# Maximizer.net
KiCad netlist of a schematic drawn in Altium Designer
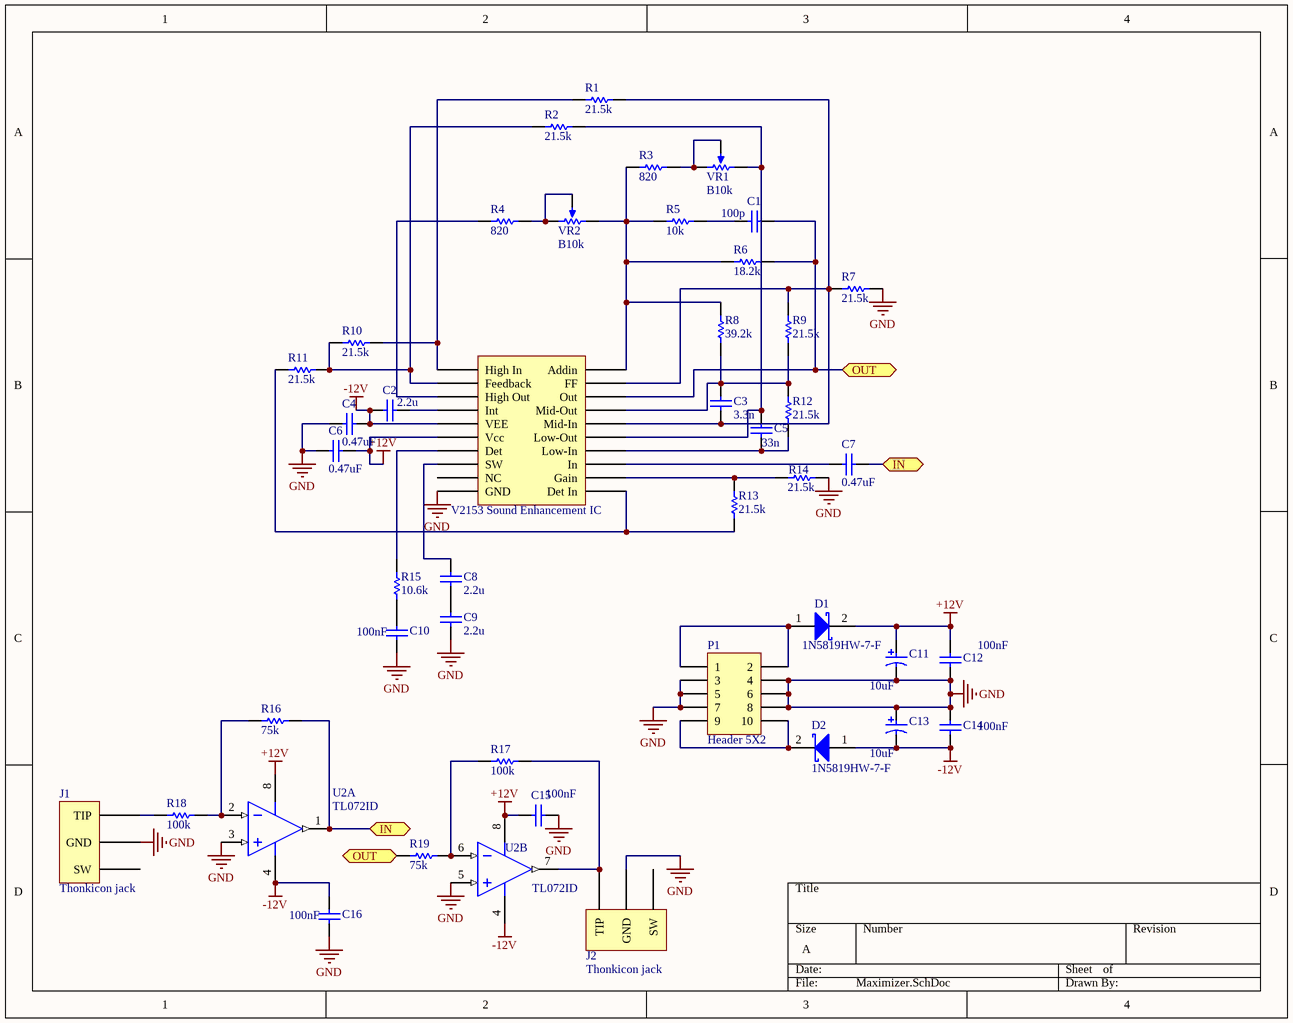
[diagram p0: Maximizer.SchDoc]

(export (version "E")
  (design (tool "Eeschema 10.0.6"))
  (components
    (comp (ref "C1")
      (value "100p")
      (footprint "CAPC0603(1608)100_M")
      (description "CAP")
      (fields (field (name "MFR") "AVX") (field (name "Comment") "100pF"))
      (libsource (lib "Altium Content Vault") (part "CMP-1035-00002-1"))
    )
    (comp (ref "C2")
      (value "2.2u")
      (footprint "CAPC0603(1608)100_M")
      (description "CAP")
      (fields (field (name "MFR") "Murata") (field (name "Comment") "2.2uF"))
      (libsource (lib "Altium Content Vault") (part "CMP-1035-00002-1"))
    )
    (comp (ref "C3")
      (value "3.3n")
      (footprint "CAPC0603(1608)100_M")
      (description "CAP")
      (fields (field (name "MFR") "AVX") (field (name "Comment") "3.3nF"))
      (libsource (lib "Altium Content Vault") (part "CMP-1035-00002-1"))
    )
    (comp (ref "C4")
      (value "0.47uF")
      (footprint "CAPC0603(1608)100_M")
      (description "CAP")
      (fields (field (name "MFR") "Murata"))
      (libsource (lib "Altium Content Vault") (part "CMP-1035-00002-1"))
    )
    (comp (ref "C5")
      (value "33n")
      (footprint "CAPC0603(1608)100_M")
      (description "CAP")
      (fields (field (name "MFR") "Murata") (field (name "Comment") "33nF"))
      (libsource (lib "Altium Content Vault") (part "CMP-1035-00002-1"))
    )
    (comp (ref "C6")
      (value "0.47uF")
      (footprint "CAPC0603(1608)100_M")
      (description "CAP")
      (fields (field (name "MFR") "Murata"))
      (libsource (lib "Altium Content Vault") (part "CMP-1035-00002-1"))
    )
    (comp (ref "C7")
      (value "0.47uF")
      (footprint "CAPC0603(1608)100_M")
      (description "CAP")
      (fields (field (name "MFR") "Murata"))
      (libsource (lib "Altium Content Vault") (part "CMP-1035-00002-1"))
    )
    (comp (ref "C8")
      (value "2.2u")
      (footprint "CAPC0603(1608)100_M")
      (description "CAP")
      (fields (field (name "MFR") "Murata") (field (name "Comment") "2.2uF"))
      (libsource (lib "Altium Content Vault") (part "CMP-1035-00002-1"))
    )
    (comp (ref "C9")
      (value "2.2u")
      (footprint "CAPC0603(1608)100_M")
      (description "CAP")
      (fields (field (name "MFR") "Murata") (field (name "Comment") "2.2uF"))
      (libsource (lib "Altium Content Vault") (part "CMP-1035-00002-1"))
    )
    (comp (ref "C10")
      (value "100nF")
      (footprint "CAPC0603(1608)100_M")
      (description "CAP")
      (fields (field (name "MFR") "AVX"))
      (libsource (lib "Altium Content Vault") (part "CMP-1035-00002-1"))
    )
    (comp (ref "C11")
      (value "10uF")
      (footprint "NIC-CAPA2-4X5.8_V")
      (fields (field (name "MFR") "Nichicon"))
      (libsource (lib "Altium Content Vault") (part "CMP-0687-00016-1"))
    )
    (comp (ref "C12")
      (value "100nF")
      (footprint "CAPC0603(1608)100_M")
      (description "CAP")
      (fields (field (name "MFR") "AVX"))
      (libsource (lib "Altium Content Vault") (part "CMP-1035-00002-1"))
    )
    (comp (ref "C13")
      (value "10uF")
      (footprint "NIC-CAPA2-4X5.8_V")
      (fields (field (name "MFR") "Nichicon"))
      (libsource (lib "Altium Content Vault") (part "CMP-0687-00016-1"))
    )
    (comp (ref "C14")
      (value "100nF")
      (footprint "CAPC0603(1608)100_M")
      (description "CAP")
      (fields (field (name "MFR") "AVX"))
      (libsource (lib "Altium Content Vault") (part "CMP-1035-00002-1"))
    )
    (comp (ref "C15")
      (value "100nF")
      (footprint "CAPC0603(1608)100_M")
      (description "CAP")
      (fields (field (name "MFR") "AVX"))
      (libsource (lib "Altium Content Vault") (part "CMP-1035-00002-1"))
    )
    (comp (ref "C16")
      (value "100nF")
      (footprint "CAPC0603(1608)100_M")
      (description "CAP")
      (fields (field (name "MFR") "AVX"))
      (libsource (lib "Altium Content Vault") (part "CMP-1035-00002-1"))
    )
    (comp (ref "D1")
      (value "1N5819HW-7-F")
      (footprint "DIOD-SOD-123-2_V")
      (fields (field (name "MFR") "Diodes Inc."))
      (libsource (lib "Altium Content Vault") (part "CMP-0303-00003-1"))
    )
    (comp (ref "D2")
      (value "1N5819HW-7-F")
      (footprint "DIOD-SOD-123-2_V")
      (fields (field (name "MFR") "Diodes Inc."))
      (libsource (lib "Altium Content Vault") (part "CMP-0303-00003-1"))
    )
    (comp (ref "J1")
      (value "Thonkicon jack")
      (footprint "Thonkiconn Pot PJ301M")
      (libsource (lib "EurrackParts") (part "Thonkicon jack"))
    )
    (comp (ref "J2")
      (value "Thonkicon jack")
      (footprint "Thonkiconn Pot PJ301M")
      (libsource (lib "") (part "Thonkicon jack_1"))
    )
    (comp (ref "P1")
      (value "Header 5X2")
      (footprint "HDR2X5")
      (description "Header, 5-Pin, Dual row")
      (fields (field (name "PUBLISHER") "Altium Limited"))
      (libsource (lib "Miscellaneous Connectors") (part "Header 5X2"))
    )
    (comp (ref "R1")
      (value "21.5k")
      (footprint "RESC0603(1608)_M")
      (description "Res")
      (fields (field (name "TOLERANCE") "5 %") (field (name "MFR") "Susumu"))
      (libsource (lib "Altium Content Vault") (part "CMP-1012-00002-1"))
    )
    (comp (ref "R2")
      (value "21.5k")
      (footprint "RESC0603(1608)_M")
      (description "Res")
      (fields (field (name "TOLERANCE") "5 %") (field (name "MFR") "Susumu"))
      (libsource (lib "Altium Content Vault") (part "CMP-1012-00002-1"))
    )
    (comp (ref "R3")
      (value "820")
      (footprint "RESC0603(1608)_M")
      (description "Res")
      (fields (field (name "TOLERANCE") "5 %") (field (name "MFR") "Susumu"))
      (libsource (lib "Altium Content Vault") (part "CMP-1012-00002-1"))
    )
    (comp (ref "R4")
      (value "820")
      (footprint "RESC0603(1608)_M")
      (description "Res")
      (fields (field (name "TOLERANCE") "5 %") (field (name "MFR") "Susumu"))
      (libsource (lib "Altium Content Vault") (part "CMP-1012-00002-1"))
    )
    (comp (ref "R5")
      (value "10k")
      (footprint "RESC0603(1608)_M")
      (description "Res")
      (fields (field (name "TOLERANCE") "5 %") (field (name "MFR") "Susumu"))
      (libsource (lib "Altium Content Vault") (part "CMP-1012-00002-1"))
    )
    (comp (ref "R6")
      (value "18.2k")
      (footprint "RESC0603(1608)_M")
      (description "Res")
      (fields (field (name "TOLERANCE") "5 %") (field (name "MFR") "Susumu"))
      (libsource (lib "Altium Content Vault") (part "CMP-1012-00002-1"))
    )
    (comp (ref "R7")
      (value "21.5k")
      (footprint "RESC0603(1608)_M")
      (description "Res")
      (fields (field (name "TOLERANCE") "5 %") (field (name "MFR") "Susumu"))
      (libsource (lib "Altium Content Vault") (part "CMP-1012-00002-1"))
    )
    (comp (ref "R8")
      (value "39.2k")
      (footprint "RESC0603(1608)_M")
      (description "Res")
      (fields (field (name "TOLERANCE") "5 %") (field (name "MFR") "KOA"))
      (libsource (lib "Altium Content Vault") (part "CMP-1012-00002-1"))
    )
    (comp (ref "R9")
      (value "21.5k")
      (footprint "RESC0603(1608)_M")
      (description "Res")
      (fields (field (name "TOLERANCE") "5 %") (field (name "MFR") "Susumu"))
      (libsource (lib "Altium Content Vault") (part "CMP-1012-00002-1"))
    )
    (comp (ref "R10")
      (value "21.5k")
      (footprint "RESC0603(1608)_M")
      (description "Res")
      (fields (field (name "TOLERANCE") "5 %") (field (name "MFR") "Susumu"))
      (libsource (lib "Altium Content Vault") (part "CMP-1012-00002-1"))
    )
    (comp (ref "R11")
      (value "21.5k")
      (footprint "RESC0603(1608)_M")
      (description "Res")
      (fields (field (name "TOLERANCE") "5 %") (field (name "MFR") "Susumu"))
      (libsource (lib "Altium Content Vault") (part "CMP-1012-00002-1"))
    )
    (comp (ref "R12")
      (value "21.5k")
      (footprint "RESC0603(1608)_M")
      (description "Res")
      (fields (field (name "TOLERANCE") "5 %") (field (name "MFR") "Susumu"))
      (libsource (lib "Altium Content Vault") (part "CMP-1012-00002-1"))
    )
    (comp (ref "R13")
      (value "21.5k")
      (footprint "RESC0603(1608)_M")
      (description "Res")
      (fields (field (name "TOLERANCE") "5 %") (field (name "MFR") "Susumu"))
      (libsource (lib "Altium Content Vault") (part "CMP-1012-00002-1"))
    )
    (comp (ref "R14")
      (value "21.5k")
      (footprint "RESC0603(1608)_M")
      (description "Res")
      (fields (field (name "TOLERANCE") "5 %") (field (name "MFR") "Susumu"))
      (libsource (lib "Altium Content Vault") (part "CMP-1012-00002-1"))
    )
    (comp (ref "R15")
      (value "10.6k")
      (footprint "RESC0603(1608)_M")
      (description "Res")
      (fields (field (name "TOLERANCE") "5 %") (field (name "MFR") "Koa"))
      (libsource (lib "Altium Content Vault") (part "CMP-1012-00002-1"))
    )
    (comp (ref "R16")
      (value "75k")
      (footprint "RESC0603(1608)_M")
      (description "Res")
      (fields (field (name "TOLERANCE") "5 %") (field (name "MFR") "Susumu"))
      (libsource (lib "Altium Content Vault") (part "CMP-1012-00002-1"))
    )
    (comp (ref "R17")
      (value "100k")
      (footprint "RESC0603(1608)_M")
      (description "Res")
      (fields (field (name "TOLERANCE") "5 %") (field (name "MFR") "Susumu"))
      (libsource (lib "Altium Content Vault") (part "CMP-1012-00002-1"))
    )
    (comp (ref "R18")
      (value "100k")
      (footprint "RESC0603(1608)_M")
      (description "Res")
      (fields (field (name "TOLERANCE") "5 %") (field (name "MFR") "Susumu"))
      (libsource (lib "Altium Content Vault") (part "CMP-1012-00002-1"))
    )
    (comp (ref "R19")
      (value "75k")
      (footprint "RESC0603(1608)_M")
      (description "Res")
      (fields (field (name "TOLERANCE") "5 %") (field (name "MFR") "Susumu"))
      (libsource (lib "Altium Content Vault") (part "CMP-1012-00002-1"))
    )
    (comp (ref "U1")
      (value "V2153 Sound Enhancement IC")
      (footprint "SOIC20 - duplicate")
      (description "V2153")
      (libsource (lib "EurrackParts") (part "CoolaudioV2153"))
    )
    (comp (ref "U2")
      (value "TL072ID")
      (footprint "D0008A_N")
      (fields (field (name "MFR") "ST Micro"))
      (libsource (lib "Altium Content Vault") (part "CMP-0015-00077-2"))
    )
    (comp (ref "VR1")
      (value "B10k")
      (footprint "SonGueiPot")
      (fields (field (name "MANUFACTURER") "Bourns") (field (name "PARTNUMBER") "3006P-7-502ZLF"))
      (libsource (lib "altium-import") (part "root_0_BOUR-3006P-3_"))
    )
    (comp (ref "VR2")
      (value "B10k")
      (footprint "SonGueiPot")
      (fields (field (name "MANUFACTURER") "Bourns") (field (name "PARTNUMBER") "3006P-7-502ZLF"))
      (libsource (lib "altium-import") (part "root_0_BOUR-3006P-3_"))
    )
  )
  (nets
    (net (code "1") (name "+12V") (class "Default")
      (node (ref "C11") (pin "1") (pinfunction "1_1") (pintype "passive"))
      (node (ref "C12") (pin "1") (pinfunction "1_1") (pintype "passive"))
      (node (ref "C15") (pin "1") (pinfunction "1_1") (pintype "passive"))
      (node (ref "C6") (pin "2") (pinfunction "2_2") (pintype "passive"))
      (node (ref "D1") (pin "2") (pinfunction "K_2") (pintype "passive"))
      (node (ref "U1") (pin "6") (pinfunction "Vcc_6") (pintype "passive"))
      (node (ref "U2") (pin "8") (pinfunction "VCC+_8") (pintype "power_in"))
    )
    (net (code "2") (name "-12V") (class "Default")
      (node (ref "C13") (pin "2") (pinfunction "2_2") (pintype "passive"))
      (node (ref "C14") (pin "2") (pinfunction "2_2") (pintype "passive"))
      (node (ref "C16") (pin "1") (pinfunction "1_1") (pintype "passive"))
      (node (ref "C2") (pin "1") (pinfunction "1_1") (pintype "passive"))
      (node (ref "C4") (pin "2") (pinfunction "2_2") (pintype "passive"))
      (node (ref "D2") (pin "1") (pinfunction "A_1") (pintype "passive"))
      (node (ref "U1") (pin "5") (pinfunction "VEE_5") (pintype "passive"))
      (node (ref "U2") (pin "4") (pinfunction "VCC-_4") (pintype "power_in"))
    )
    (net (code "3") (name "/IN") (class "Default")
      (node (ref "C7") (pin "2") (pinfunction "2_2") (pintype "passive"))
      (node (ref "R16") (pin "1") (pinfunction "1_1") (pintype "passive"))
      (node (ref "U2") (pin "1") (pinfunction "OUT1_1") (pintype "output"))
    )
    (net (code "4") (name "/OUT") (class "Default")
      (node (ref "C1") (pin "2") (pinfunction "2_2") (pintype "passive"))
      (node (ref "R19") (pin "2") (pinfunction "2_2") (pintype "passive"))
      (node (ref "R6") (pin "1") (pinfunction "1_1") (pintype "passive"))
      (node (ref "U1") (pin "18") (pinfunction "Out_18") (pintype "passive"))
    )
    (net (code "5") (name "GND") (class "Default")
      (node (ref "C10") (pin "2") (pinfunction "2_2") (pintype "passive"))
      (node (ref "C11") (pin "2") (pinfunction "2_2") (pintype "passive"))
      (node (ref "C12") (pin "2") (pinfunction "2_2") (pintype "passive"))
      (node (ref "C13") (pin "1") (pinfunction "1_1") (pintype "passive"))
      (node (ref "C14") (pin "1") (pinfunction "1_1") (pintype "passive"))
      (node (ref "C15") (pin "2") (pinfunction "2_2") (pintype "passive"))
      (node (ref "C16") (pin "2") (pinfunction "2_2") (pintype "passive"))
      (node (ref "C4") (pin "1") (pinfunction "1_1") (pintype "passive"))
      (node (ref "C6") (pin "1") (pinfunction "1_1") (pintype "passive"))
      (node (ref "C9") (pin "1") (pinfunction "1_1") (pintype "passive"))
      (node (ref "J1") (pin "1") (pinfunction "GND_1") (pintype "passive"))
      (node (ref "J2") (pin "1") (pinfunction "GND_1") (pintype "passive"))
      (node (ref "P1") (pin "3") (pinfunction "3_3") (pintype "passive"))
      (node (ref "P1") (pin "4") (pinfunction "4_4") (pintype "passive"))
      (node (ref "P1") (pin "5") (pinfunction "5_5") (pintype "passive"))
      (node (ref "P1") (pin "6") (pinfunction "6_6") (pintype "passive"))
      (node (ref "P1") (pin "7") (pinfunction "7_7") (pintype "passive"))
      (node (ref "P1") (pin "8") (pinfunction "8_8") (pintype "passive"))
      (node (ref "R14") (pin "1") (pinfunction "1_1") (pintype "passive"))
      (node (ref "R7") (pin "1") (pinfunction "1_1") (pintype "passive"))
      (node (ref "U1") (pin "10") (pinfunction "GND_10") (pintype "passive"))
      (node (ref "U2") (pin "3") (pinfunction "IN1+_3") (pintype "input"))
      (node (ref "U2") (pin "5") (pinfunction "IN2+_5") (pintype "input"))
    )
    (net (code "6") (name "Net-(C1-Pad1)") (class "Default")
      (node (ref "C1") (pin "1") (pinfunction "1_1") (pintype "passive"))
      (node (ref "R5") (pin "1") (pinfunction "1_1") (pintype "passive"))
    )
    (net (code "7") (name "Net-(C8-Pad1)") (class "Default")
      (node (ref "C8") (pin "1") (pinfunction "1_1") (pintype "passive"))
      (node (ref "C9") (pin "2") (pinfunction "2_2") (pintype "passive"))
    )
    (net (code "8") (name "Net-(C10-Pad1)") (class "Default")
      (node (ref "C10") (pin "1") (pinfunction "1_1") (pintype "passive"))
      (node (ref "R15") (pin "1") (pinfunction "1_1") (pintype "passive"))
    )
    (net (code "9") (name "Net-(D1-A)") (class "Default")
      (node (ref "D1") (pin "1") (pinfunction "A_1") (pintype "passive"))
      (node (ref "P1") (pin "1") (pinfunction "1_1") (pintype "passive"))
      (node (ref "P1") (pin "2") (pinfunction "2_2") (pintype "passive"))
    )
    (net (code "10") (name "Net-(D2-K)") (class "Default")
      (node (ref "D2") (pin "2") (pinfunction "K_2") (pintype "passive"))
      (node (ref "P1") (pin "10") (pinfunction "10_10") (pintype "passive"))
      (node (ref "P1") (pin "9") (pinfunction "9_9") (pintype "passive"))
    )
    (net (code "11") (name "Net-(J1-TIP)") (class "Default")
      (node (ref "J1") (pin "3") (pinfunction "TIP_3") (pintype "passive"))
      (node (ref "R18") (pin "2") (pinfunction "2_2") (pintype "passive"))
    )
    (net (code "12") (name "Net-(J2-TIP)") (class "Default")
      (node (ref "J2") (pin "3") (pinfunction "TIP_3") (pintype "passive"))
      (node (ref "R17") (pin "1") (pinfunction "1_1") (pintype "passive"))
      (node (ref "U2") (pin "7") (pinfunction "OUT2_7") (pintype "output"))
    )
    (net (code "13") (name "Net-(U1-Addin)") (class "Default")
      (node (ref "R3") (pin "2") (pinfunction "2_2") (pintype "passive"))
      (node (ref "R5") (pin "2") (pinfunction "2_2") (pintype "passive"))
      (node (ref "R6") (pin "2") (pinfunction "2_2") (pintype "passive"))
      (node (ref "R8") (pin "2") (pinfunction "2_2") (pintype "passive"))
      (node (ref "U1") (pin "20") (pinfunction "Addin_20") (pintype "passive"))
      (node (ref "VR2") (pin "3") (pinfunction "CW_3") (pintype "passive"))
    )
    (net (code "14") (name "Net-(U1-Det)") (class "Default")
      (node (ref "R15") (pin "2") (pinfunction "2_2") (pintype "passive"))
      (node (ref "U1") (pin "7") (pinfunction "Det_7") (pintype "passive"))
    )
    (net (code "15") (name "Net-(U1-Det_In)") (class "Default")
      (node (ref "R11") (pin "2") (pinfunction "2_2") (pintype "passive"))
      (node (ref "R13") (pin "2") (pinfunction "2_2") (pintype "passive"))
      (node (ref "U1") (pin "11") (pinfunction "Det_In_11") (pintype "passive"))
    )
    (net (code "16") (name "Net-(U1-FF)") (class "Default")
      (node (ref "C3") (pin "1") (pinfunction "1_1") (pintype "passive"))
      (node (ref "R1") (pin "1") (pinfunction "1_1") (pintype "passive"))
      (node (ref "R7") (pin "2") (pinfunction "2_2") (pintype "passive"))
      (node (ref "R9") (pin "1") (pinfunction "1_1") (pintype "passive"))
      (node (ref "U1") (pin "16") (pinfunction "Mid-In_16") (pintype "passive"))
      (node (ref "U1") (pin "19") (pinfunction "FF_19") (pintype "passive"))
    )
    (net (code "17") (name "Net-(U1-Feedback)") (class "Default")
      (node (ref "R10") (pin "2") (pinfunction "2_2") (pintype "passive"))
      (node (ref "R11") (pin "1") (pinfunction "1_1") (pintype "passive"))
      (node (ref "R2") (pin "2") (pinfunction "2_2") (pintype "passive"))
      (node (ref "U1") (pin "2") (pinfunction "Feedback_2") (pintype "passive"))
    )
    (net (code "18") (name "Net-(U1-Gain)") (class "Default")
      (node (ref "R13") (pin "1") (pinfunction "1_1") (pintype "passive"))
      (node (ref "R14") (pin "2") (pinfunction "2_2") (pintype "passive"))
      (node (ref "U1") (pin "12") (pinfunction "Gain_12") (pintype "passive"))
    )
    (net (code "19") (name "Net-(U1-High_In)") (class "Default")
      (node (ref "R1") (pin "2") (pinfunction "2_2") (pintype "passive"))
      (node (ref "R10") (pin "1") (pinfunction "1_1") (pintype "passive"))
      (node (ref "U1") (pin "1") (pinfunction "High_In_1") (pintype "passive"))
    )
    (net (code "20") (name "Net-(U1-High_Out)") (class "Default")
      (node (ref "R4") (pin "2") (pinfunction "2_2") (pintype "passive"))
      (node (ref "U1") (pin "3") (pinfunction "High_Out_3") (pintype "passive"))
    )
    (net (code "21") (name "Net-(U1-In)") (class "Default")
      (node (ref "C7") (pin "1") (pinfunction "1_1") (pintype "passive"))
      (node (ref "U1") (pin "13") (pinfunction "In_13") (pintype "passive"))
    )
    (net (code "22") (name "Net-(U1-Int)") (class "Default")
      (node (ref "C2") (pin "2") (pinfunction "2_2") (pintype "passive"))
      (node (ref "U1") (pin "4") (pinfunction "Int_4") (pintype "passive"))
    )
    (net (code "23") (name "Net-(U1-Low-In)") (class "Default")
      (node (ref "C5") (pin "1") (pinfunction "1_1") (pintype "passive"))
      (node (ref "R12") (pin "2") (pinfunction "2_2") (pintype "passive"))
      (node (ref "U1") (pin "14") (pinfunction "Low-In_14") (pintype "passive"))
    )
    (net (code "24") (name "Net-(U1-Low-Out)") (class "Default")
      (node (ref "C5") (pin "2") (pinfunction "2_2") (pintype "passive"))
      (node (ref "R2") (pin "1") (pinfunction "1_1") (pintype "passive"))
      (node (ref "U1") (pin "15") (pinfunction "Low-Out_15") (pintype "passive"))
      (node (ref "VR1") (pin "3") (pinfunction "CW_3") (pintype "passive"))
    )
    (net (code "25") (name "Net-(U1-Mid-Out)") (class "Default")
      (node (ref "C3") (pin "2") (pinfunction "2_2") (pintype "passive"))
      (node (ref "R12") (pin "1") (pinfunction "1_1") (pintype "passive"))
      (node (ref "R8") (pin "1") (pinfunction "1_1") (pintype "passive"))
      (node (ref "R9") (pin "2") (pinfunction "2_2") (pintype "passive"))
      (node (ref "U1") (pin "17") (pinfunction "Mid-Out_17") (pintype "passive"))
    )
    (net (code "26") (name "Net-(U1-SW)") (class "Default")
      (node (ref "C8") (pin "2") (pinfunction "2_2") (pintype "passive"))
      (node (ref "U1") (pin "8") (pinfunction "SW_8") (pintype "passive"))
    )
    (net (code "27") (name "Net-(U2A-IN1-)") (class "Default")
      (node (ref "R16") (pin "2") (pinfunction "2_2") (pintype "passive"))
      (node (ref "R18") (pin "1") (pinfunction "1_1") (pintype "passive"))
      (node (ref "U2") (pin "2") (pinfunction "IN1-_2") (pintype "input"))
    )
    (net (code "28") (name "Net-(U2B-IN2-)") (class "Default")
      (node (ref "R17") (pin "2") (pinfunction "2_2") (pintype "passive"))
      (node (ref "R19") (pin "1") (pinfunction "1_1") (pintype "passive"))
      (node (ref "U2") (pin "6") (pinfunction "IN2-_6") (pintype "input"))
    )
    (net (code "29") (name "Net-(VR1-CCW)") (class "Default")
      (node (ref "R3") (pin "1") (pinfunction "1_1") (pintype "passive"))
      (node (ref "VR1") (pin "1") (pinfunction "CCW_1") (pintype "passive"))
      (node (ref "VR1") (pin "2") (pinfunction "WIPER_2") (pintype "passive"))
    )
    (net (code "30") (name "Net-(VR2-CCW)") (class "Default")
      (node (ref "R4") (pin "1") (pinfunction "1_1") (pintype "passive"))
      (node (ref "VR2") (pin "1") (pinfunction "CCW_1") (pintype "passive"))
      (node (ref "VR2") (pin "2") (pinfunction "WIPER_2") (pintype "passive"))
    )
    (net (code "31") (name "unconnected-(J1-SW-Pad2)") (class "Default")
      (node (ref "J1") (pin "2") (pinfunction "SW_2") (pintype "passive"))
    )
    (net (code "32") (name "unconnected-(J2-SW-Pad2)") (class "Default")
      (node (ref "J2") (pin "2") (pinfunction "SW_2") (pintype "passive"))
    )
    (net (code "33") (name "unconnected-(U1-NC-Pad9)") (class "Default")
      (node (ref "U1") (pin "9") (pinfunction "NC_9") (pintype "passive"))
    )
  )
)
